# Power.net
KiCad netlist of a schematic drawn in Altium Designer
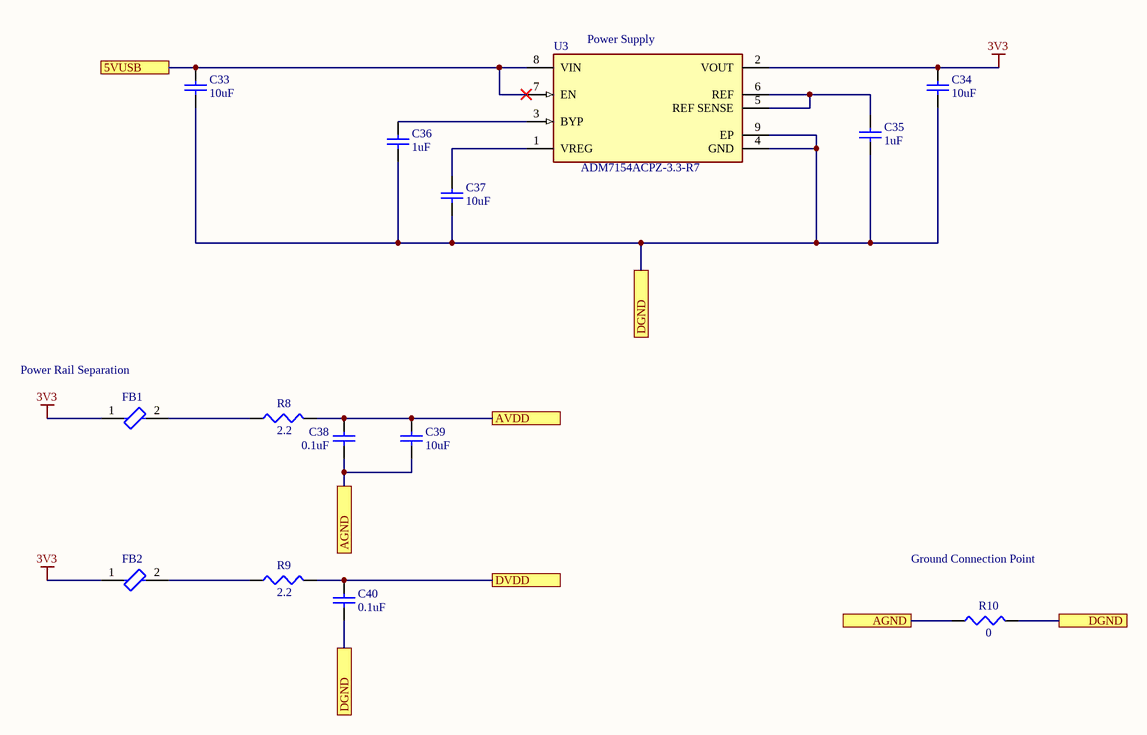
[diagram p0: Power.SchDoc]

(export (version "E")
  (design (tool "Eeschema 10.0.6"))
  (components
    (comp (ref "C33")
      (value "10uF")
      (footprint "0402 SMD")
      (description "10 µF ±20% 6.3V Ceramic Capacitor X5R 0402 (1005 Metric) (1005 Metric) Kemet")
      (fields (field (name "Comment") "C0402C106M9PAC7867"))
      (libsource (lib "ACEstat") (part "C0402C106M9PAC7867"))
    )
    (comp (ref "C34")
      (value "10uF")
      (footprint "0402 SMD")
      (description "10 µF ±20% 6.3V Ceramic Capacitor X5R 0402 (1005 Metric) (1005 Metric) Kemet")
      (fields (field (name "Comment") "C0402C106M9PAC7867"))
      (libsource (lib "ACEstat") (part "C0402C106M9PAC7867"))
    )
    (comp (ref "C35")
      (value "1uF")
      (footprint "0402 SMD")
      (description "1 µF ±10% 10V Ceramic Capacitor X5R 0402 (1005 Metric)")
      (fields (field (name "Comment") "C0402C105K8PAC7867"))
      (libsource (lib "ACEstat") (part "C0402C105K8PAC7867"))
    )
    (comp (ref "C36")
      (value "1uF")
      (footprint "0402 SMD")
      (description "1 µF ±10% 10V Ceramic Capacitor X5R 0402 (1005 Metric)")
      (fields (field (name "Comment") "C0402C105K8PAC7867"))
      (libsource (lib "ACEstat") (part "C0402C105K8PAC7867"))
    )
    (comp (ref "C37")
      (value "10uF")
      (footprint "0402 SMD")
      (description "10 µF ±20% 6.3V Ceramic Capacitor X5R 0402 (1005 Metric) (1005 Metric) Kemet")
      (fields (field (name "Comment") "C0402C106M9PAC7867"))
      (libsource (lib "ACEstat") (part "C0402C106M9PAC7867"))
    )
    (comp (ref "C38")
      (value "0.1uF")
      (footprint "0402 SMD")
      (description "0.1 µF ±10% 16V Ceramic Capacitor X7R 0402 (1005 Metric) Kemet")
      (fields (field (name "Comment") "C0402C104K4RAC7867"))
      (libsource (lib "ACEstat") (part "C0402C104K4RAC7867"))
    )
    (comp (ref "C39")
      (value "10uF")
      (footprint "0402 SMD")
      (description "10 µF ±20% 6.3V Ceramic Capacitor X5R 0402 (1005 Metric) (1005 Metric) Kemet")
      (fields (field (name "Comment") "C0402C106M9PAC7867"))
      (libsource (lib "ACEstat") (part "C0402C106M9PAC7867"))
    )
    (comp (ref "C40")
      (value "0.1uF")
      (footprint "0402 SMD")
      (description "0.1 µF ±10% 16V Ceramic Capacitor X7R 0402 (1005 Metric) Kemet")
      (fields (field (name "Comment") "C0402C104K4RAC7867"))
      (libsource (lib "ACEstat") (part "C0402C104K4RAC7867"))
    )
    (comp (ref "FB1")
      (value "BLM15PD600SN1D")
      (footprint "FP-BLM15-0_05-d0_7-IPC_B")
      (description "Chip Ferrite Bead, 0402, 60Ω @ 100MHz, 0.06Ω, 25%, 1.7A")
      (fields (field (name "TOLERANCE") "25%"))
      (libsource (lib "Altium Content Vault") (part "5f30dd21d616792df468990f7003faa"))
    )
    (comp (ref "FB2")
      (value "BLM15PD600SN1D")
      (footprint "FP-BLM15-0_05-d0_7-IPC_B")
      (description "Chip Ferrite Bead, 0402, 60Ω @ 100MHz, 0.06Ω, 25%, 1.7A")
      (fields (field (name "TOLERANCE") "25%"))
      (libsource (lib "Altium Content Vault") (part "5f30dd21d616792df468990f7003faa"))
    )
    (comp (ref "R8")
      (value "2.2")
      (footprint "0402 SMD")
      (fields (field (name "Comment") "SG73P1EWTTP2R20F"))
      (libsource (lib "ACEstat") (part "SG73P1EWTTP2R20F"))
    )
    (comp (ref "R9")
      (value "2.2")
      (footprint "0402 SMD")
      (fields (field (name "Comment") "SG73P1EWTTP2R20F"))
      (libsource (lib "ACEstat") (part "SG73P1EWTTP2R20F"))
    )
    (comp (ref "R10")
      (value "0")
      (footprint "0402 SMD")
      (description "0 Ohms Jumper 0.063W, 1/16W Chip Resistor 0402 (1005 Metric) Moisture Resistant Thick Film")
      (fields (field (name "Comment") "RC0402FR-070RL"))
      (libsource (lib "ACEstat") (part "RC0402FR-070RL"))
    )
    (comp (ref "U3")
      (value "ADM7154ACPZ-3.3-R7")
      (footprint "FP-CP-8-21-IPC_C")
      (description "IC REG LINEAR 3.3V 600MA 8LFCSP")
      (libsource (lib "Altium Content Vault") (part "b1ac0f4a616aa71f3e8703c652d4fec"))
    )
  )
  (nets
    (net (code "1") (name "/5VUSB") (class "Default")
      (node (ref "C33") (pin "2") (pinfunction "2_2") (pintype "passive"))
      (node (ref "U3") (pin "7") (pinfunction "EN_7") (pintype "input"))
      (node (ref "U3") (pin "8") (pinfunction "VIN_8") (pintype "power_in"))
    )
    (net (code "2") (name "/AGND") (class "Default")
      (node (ref "C38") (pin "1") (pinfunction "1_1") (pintype "passive"))
      (node (ref "C39") (pin "1") (pinfunction "1_1") (pintype "passive"))
      (node (ref "R10") (pin "1") (pinfunction "1_1") (pintype "passive"))
    )
    (net (code "3") (name "/AVDD") (class "Default")
      (node (ref "C38") (pin "2") (pinfunction "2_2") (pintype "passive"))
      (node (ref "C39") (pin "2") (pinfunction "2_2") (pintype "passive"))
      (node (ref "R8") (pin "2") (pinfunction "2_2") (pintype "passive"))
    )
    (net (code "4") (name "/DGND") (class "Default")
      (node (ref "C33") (pin "1") (pinfunction "1_1") (pintype "passive"))
      (node (ref "C34") (pin "1") (pinfunction "1_1") (pintype "passive"))
      (node (ref "C35") (pin "1") (pinfunction "1_1") (pintype "passive"))
      (node (ref "C36") (pin "1") (pinfunction "1_1") (pintype "passive"))
      (node (ref "C37") (pin "1") (pinfunction "1_1") (pintype "passive"))
      (node (ref "C40") (pin "1") (pinfunction "1_1") (pintype "passive"))
      (node (ref "R10") (pin "2") (pinfunction "2_2") (pintype "passive"))
      (node (ref "U3") (pin "4") (pinfunction "GND_4") (pintype "power_in"))
      (node (ref "U3") (pin "9") (pinfunction "EP_9") (pintype "passive"))
    )
    (net (code "5") (name "/DVDD") (class "Default")
      (node (ref "C40") (pin "2") (pinfunction "2_2") (pintype "passive"))
      (node (ref "R9") (pin "2") (pinfunction "2_2") (pintype "passive"))
    )
    (net (code "6") (name "3V3") (class "Default")
      (node (ref "C34") (pin "2") (pinfunction "2_2") (pintype "passive"))
      (node (ref "FB1") (pin "1") (pinfunction "1_1") (pintype "passive"))
      (node (ref "FB2") (pin "1") (pinfunction "1_1") (pintype "passive"))
      (node (ref "U3") (pin "2") (pinfunction "VOUT_2") (pintype "passive"))
    )
    (net (code "7") (name "Net-(FB1-Pad2)") (class "Default")
      (node (ref "FB1") (pin "2") (pinfunction "2_2") (pintype "passive"))
      (node (ref "R8") (pin "1") (pinfunction "1_1") (pintype "passive"))
    )
    (net (code "8") (name "Net-(FB2-Pad2)") (class "Default")
      (node (ref "FB2") (pin "2") (pinfunction "2_2") (pintype "passive"))
      (node (ref "R9") (pin "1") (pinfunction "1_1") (pintype "passive"))
    )
    (net (code "9") (name "Net-(U3-BYP)") (class "Default")
      (node (ref "C36") (pin "2") (pinfunction "2_2") (pintype "passive"))
      (node (ref "U3") (pin "3") (pinfunction "BYP_3") (pintype "input"))
    )
    (net (code "10") (name "Net-(U3-REF)") (class "Default")
      (node (ref "C35") (pin "2") (pinfunction "2_2") (pintype "passive"))
      (node (ref "U3") (pin "5") (pinfunction "REF_SENSE_5") (pintype "passive"))
      (node (ref "U3") (pin "6") (pinfunction "REF_6") (pintype "passive"))
    )
    (net (code "11") (name "Net-(U3-VREG)") (class "Default")
      (node (ref "C37") (pin "2") (pinfunction "2_2") (pintype "passive"))
      (node (ref "U3") (pin "1") (pinfunction "VREG_1") (pintype "power_in"))
    )
  )
)
